# SCH_SDCARD-DOCK_2024-07-07.net
KiCad netlist of a schematic drawn in EasyEDA
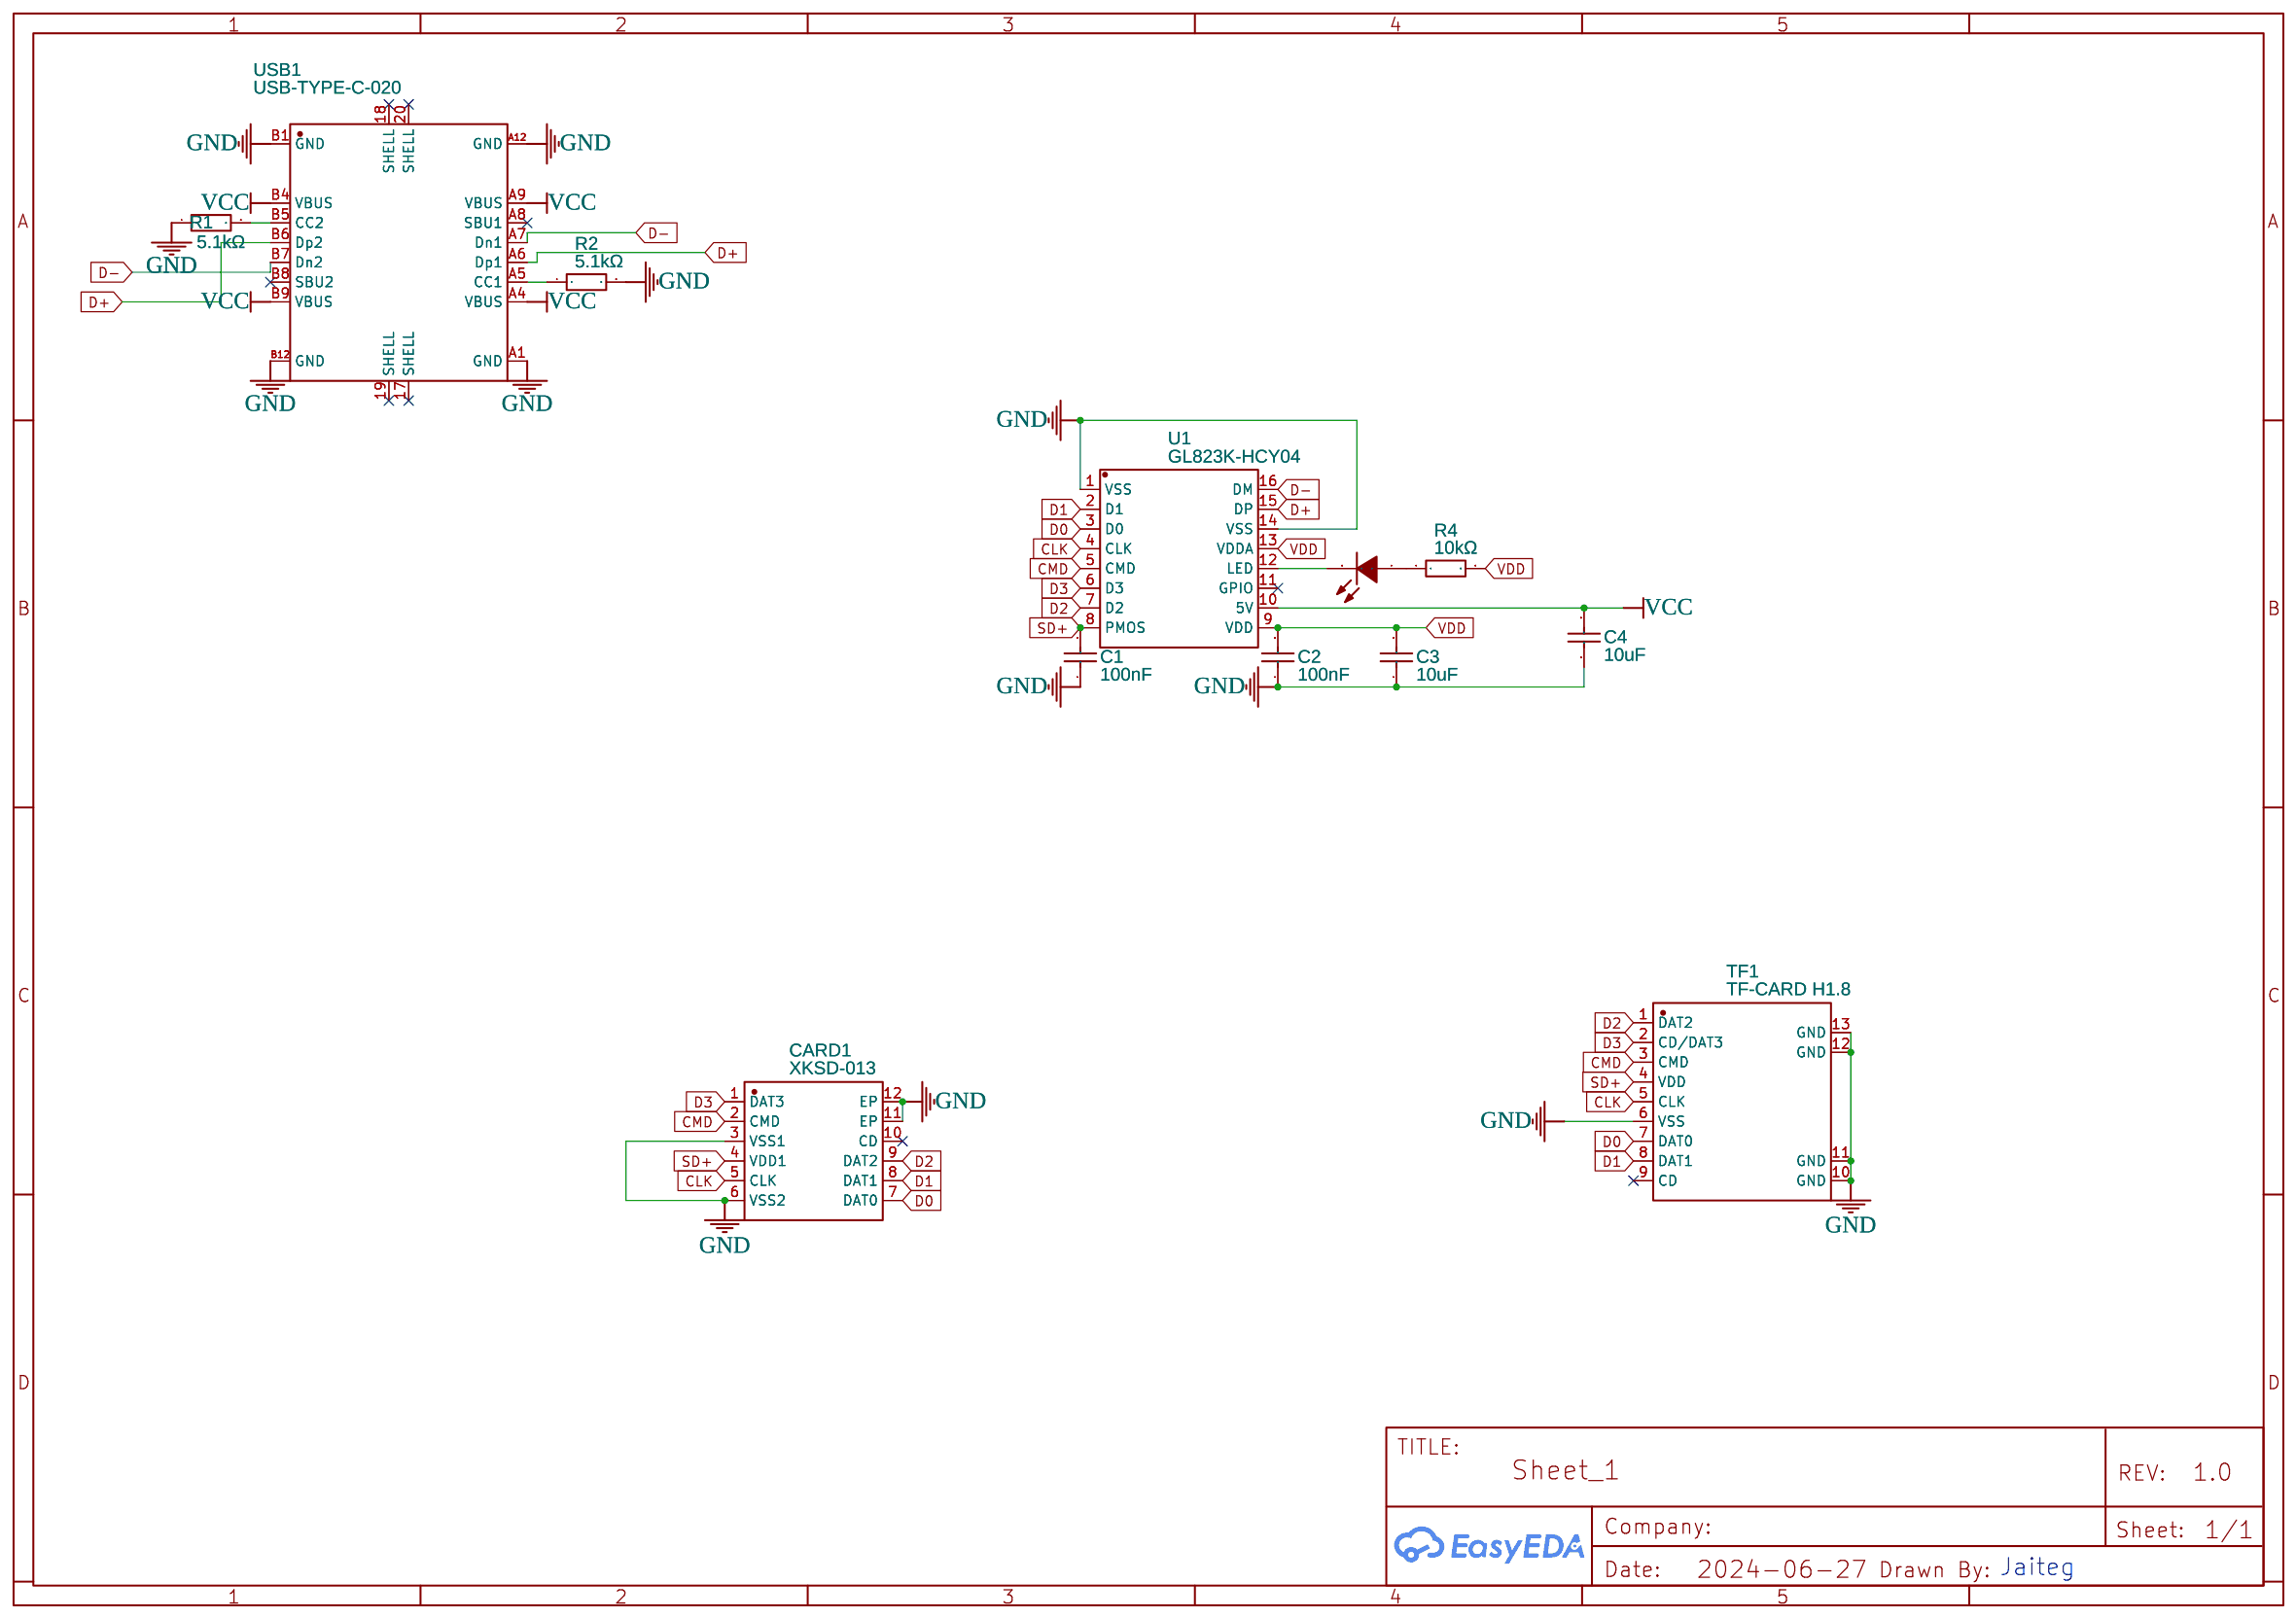
[diagram p0: schematic sheet]

(export (version "E")
  (design (tool "Eeschema 10.0.6"))
  (components
    (comp (ref "C1")
      (value "100nF")
      (fields
        (field (name "Manufacturer Part") "CL05B104KO5NNNC")
        (field (name "Manufacturer") "SAMSUNG(三星)")
      )
      (libsource (lib "") (part "CL05B104KO5NNNC"))
    )
    (comp (ref "C2")
      (value "100nF")
      (fields
        (field (name "Manufacturer Part") "CL05B104KO5NNNC")
        (field (name "Manufacturer") "SAMSUNG(三星)")
      )
      (libsource (lib "") (part "CL05B104KO5NNNC"))
    )
    (comp (ref "C3")
      (value "10uF")
      (fields
        (field (name "Manufacturer Part") "CL05A106MQ5NUNC")
        (field (name "Manufacturer") "SAMSUNG(三星)")
      )
      (libsource (lib "") (part "CL05A106MQ5NUNC"))
    )
    (comp (ref "C4")
      (value "10uF")
      (fields
        (field (name "Manufacturer Part") "CL05A106MQ5NUNC")
        (field (name "Manufacturer") "SAMSUNG(三星)")
      )
      (libsource (lib "") (part "CL05A106MQ5NUNC"))
    )
    (comp (ref "CARD1")
      (value "XKSD-013")
      (fields (field (name "Manufacturer") "XKB Connectivity(中国星坤)"))
      (libsource (lib "") (part "XKSD-013"))
    )
    (comp (ref "LED2")
      (value "0603White light_C2290")
      (fields (field (name "Manufacturer Part") "KT-0603白灯") (field (name "Manufacturer") "KENTO"))
      (libsource (lib "") (part "0603White light_C2290"))
    )
    (comp (ref "R1")
      (value "5.1kΩ")
      (fields
        (field (name "Manufacturer Part") "0402WGF5101TCE")
        (field (name "Manufacturer") "UNI-ROYAL(厚声)")
      )
      (libsource (lib "") (part "0402WGF5101TCE"))
    )
    (comp (ref "R2")
      (value "5.1kΩ")
      (fields
        (field (name "Manufacturer Part") "0402WGF5101TCE")
        (field (name "Manufacturer") "UNI-ROYAL(厚声)")
      )
      (libsource (lib "") (part "0402WGF5101TCE"))
    )
    (comp (ref "R4")
      (value "10kΩ")
      (fields
        (field (name "Manufacturer Part") "0805W8F1002T5E")
        (field (name "Manufacturer") "UNI-ROYAL(厚声)")
      )
      (libsource (lib "") (part "0805W8F1002T5E"))
    )
    (comp (ref "TF1")
      (value "TF-CARD H1.8")
      (fields (field (name "Manufacturer") "SHOU HAN(首韩)"))
      (libsource (lib "") (part "TF-CARD H1.8"))
    )
    (comp (ref "U1")
      (value "GL823K-HCY04")
      (fields (field (name "Manufacturer") "GENESYS(创惟)"))
      (libsource (lib "") (part "GL823K-HCY04"))
    )
    (comp (ref "USB1")
      (value "USB-TYPE-C-020")
      (fields (field (name "Manufacturer") "DEALON(德艺隆)"))
      (libsource (lib "") (part "USB-TYPE-C-020"))
    )
  )
  (nets
    (net (code "1") (name "CLK") (class "Default")
      (node (ref "CARD1") (pin "5") (pinfunction "CLK_5") (pintype "unspecified"))
      (node (ref "TF1") (pin "5") (pinfunction "CLK_5") (pintype "unspecified"))
      (node (ref "U1") (pin "4") (pinfunction "CLK_4") (pintype "unspecified"))
    )
    (net (code "2") (name "CMD") (class "Default")
      (node (ref "CARD1") (pin "2") (pinfunction "CMD_2") (pintype "unspecified"))
      (node (ref "TF1") (pin "3") (pinfunction "CMD_3") (pintype "unspecified"))
      (node (ref "U1") (pin "5") (pinfunction "CMD_5") (pintype "unspecified"))
    )
    (net (code "3") (name "D+") (class "Default")
      (node (ref "U1") (pin "15") (pinfunction "DP_15") (pintype "unspecified"))
      (node (ref "USB1") (pin "A6") (pinfunction "Dp1_A6") (pintype "unspecified"))
      (node (ref "USB1") (pin "B6") (pinfunction "Dp2_B6") (pintype "unspecified"))
    )
    (net (code "4") (name "D-") (class "Default")
      (node (ref "U1") (pin "16") (pinfunction "DM_16") (pintype "unspecified"))
      (node (ref "USB1") (pin "A7") (pinfunction "Dn1_A7") (pintype "unspecified"))
      (node (ref "USB1") (pin "B7") (pinfunction "Dn2_B7") (pintype "unspecified"))
    )
    (net (code "5") (name "D0") (class "Default")
      (node (ref "CARD1") (pin "7") (pinfunction "DAT0_7") (pintype "unspecified"))
      (node (ref "TF1") (pin "7") (pinfunction "DAT0_7") (pintype "unspecified"))
      (node (ref "U1") (pin "3") (pinfunction "D0_3") (pintype "unspecified"))
    )
    (net (code "6") (name "D1") (class "Default")
      (node (ref "CARD1") (pin "8") (pinfunction "DAT1_8") (pintype "unspecified"))
      (node (ref "TF1") (pin "8") (pinfunction "DAT1_8") (pintype "unspecified"))
      (node (ref "U1") (pin "2") (pinfunction "D1_2") (pintype "unspecified"))
    )
    (net (code "7") (name "D2") (class "Default")
      (node (ref "CARD1") (pin "9") (pinfunction "DAT2_9") (pintype "unspecified"))
      (node (ref "TF1") (pin "1") (pinfunction "DAT2_1") (pintype "unspecified"))
      (node (ref "U1") (pin "7") (pinfunction "D2_7") (pintype "unspecified"))
    )
    (net (code "8") (name "D3") (class "Default")
      (node (ref "CARD1") (pin "1") (pinfunction "DAT3_1") (pintype "unspecified"))
      (node (ref "TF1") (pin "2") (pinfunction "CD/DAT3_2") (pintype "unspecified"))
      (node (ref "U1") (pin "6") (pinfunction "D3_6") (pintype "unspecified"))
    )
    (net (code "9") (name "GND") (class "Default")
      (node (ref "C1") (pin "1") (pinfunction "1_1") (pintype "input"))
      (node (ref "C2") (pin "1") (pinfunction "1_1") (pintype "input"))
      (node (ref "C3") (pin "1") (pinfunction "1_1") (pintype "input"))
      (node (ref "C4") (pin "1") (pinfunction "1_1") (pintype "input"))
      (node (ref "CARD1") (pin "11") (pinfunction "EP_11") (pintype "unspecified"))
      (node (ref "CARD1") (pin "12") (pinfunction "EP_12") (pintype "unspecified"))
      (node (ref "CARD1") (pin "3") (pinfunction "VSS1_3") (pintype "unspecified"))
      (node (ref "CARD1") (pin "6") (pinfunction "VSS2_6") (pintype "unspecified"))
      (node (ref "R1") (pin "1") (pinfunction "1_1") (pintype "input"))
      (node (ref "R2") (pin "2") (pinfunction "2_2") (pintype "input"))
      (node (ref "TF1") (pin "10") (pinfunction "GND_10") (pintype "unspecified"))
      (node (ref "TF1") (pin "11") (pinfunction "GND_11") (pintype "unspecified"))
      (node (ref "TF1") (pin "12") (pinfunction "GND_12") (pintype "unspecified"))
      (node (ref "TF1") (pin "13") (pinfunction "GND_13") (pintype "unspecified"))
      (node (ref "TF1") (pin "6") (pinfunction "VSS_6") (pintype "unspecified"))
      (node (ref "U1") (pin "1") (pinfunction "VSS_1") (pintype "unspecified"))
      (node (ref "U1") (pin "14") (pinfunction "VSS_14") (pintype "unspecified"))
      (node (ref "USB1") (pin "A1") (pinfunction "GND_A1") (pintype "unspecified"))
      (node (ref "USB1") (pin "A12") (pinfunction "GND_A12") (pintype "unspecified"))
      (node (ref "USB1") (pin "B1") (pinfunction "GND_B1") (pintype "unspecified"))
      (node (ref "USB1") (pin "B12") (pinfunction "GND_B12") (pintype "unspecified"))
    )
    (net (code "10") (name "Net-(LED2-A)") (class "Default")
      (node (ref "LED2") (pin "1") (pinfunction "A_1") (pintype "unspecified"))
      (node (ref "R4") (pin "1") (pinfunction "1_1") (pintype "input"))
    )
    (net (code "11") (name "Net-(LED2-K)") (class "Default")
      (node (ref "LED2") (pin "2") (pinfunction "K_2") (pintype "unspecified"))
      (node (ref "U1") (pin "12") (pinfunction "LED_12") (pintype "unspecified"))
    )
    (net (code "12") (name "Net-(USB1-CC1)") (class "Default")
      (node (ref "R2") (pin "1") (pinfunction "1_1") (pintype "input"))
      (node (ref "USB1") (pin "A5") (pinfunction "CC1_A5") (pintype "unspecified"))
    )
    (net (code "13") (name "Net-(USB1-CC2)") (class "Default")
      (node (ref "R1") (pin "2") (pinfunction "2_2") (pintype "input"))
      (node (ref "USB1") (pin "B5") (pinfunction "CC2_B5") (pintype "unspecified"))
    )
    (net (code "14") (name "SD+") (class "Default")
      (node (ref "C1") (pin "2") (pinfunction "2_2") (pintype "input"))
      (node (ref "CARD1") (pin "4") (pinfunction "VDD1_4") (pintype "unspecified"))
      (node (ref "TF1") (pin "4") (pinfunction "VDD_4") (pintype "unspecified"))
      (node (ref "U1") (pin "8") (pinfunction "PMOS_8") (pintype "unspecified"))
    )
    (net (code "15") (name "VCC") (class "Default")
      (node (ref "C4") (pin "2") (pinfunction "2_2") (pintype "input"))
      (node (ref "U1") (pin "10") (pinfunction "5V_10") (pintype "unspecified"))
      (node (ref "USB1") (pin "A4") (pinfunction "VBUS_A4") (pintype "unspecified"))
      (node (ref "USB1") (pin "A9") (pinfunction "VBUS_A9") (pintype "unspecified"))
      (node (ref "USB1") (pin "B4") (pinfunction "VBUS_B4") (pintype "unspecified"))
      (node (ref "USB1") (pin "B9") (pinfunction "VBUS_B9") (pintype "unspecified"))
    )
    (net (code "16") (name "VDD") (class "Default")
      (node (ref "C2") (pin "2") (pinfunction "2_2") (pintype "input"))
      (node (ref "C3") (pin "2") (pinfunction "2_2") (pintype "input"))
      (node (ref "R4") (pin "2") (pinfunction "2_2") (pintype "input"))
      (node (ref "U1") (pin "13") (pinfunction "VDDA_13") (pintype "unspecified"))
      (node (ref "U1") (pin "9") (pinfunction "VDD_9") (pintype "unspecified"))
    )
    (net (code "17") (name "unconnected-(CARD1-CD-Pad10)") (class "Default")
      (node (ref "CARD1") (pin "10") (pinfunction "CD_10") (pintype "unspecified+no_connect"))
    )
    (net (code "18") (name "unconnected-(TF1-CD-Pad9)") (class "Default")
      (node (ref "TF1") (pin "9") (pinfunction "CD_9") (pintype "unspecified+no_connect"))
    )
    (net (code "19") (name "unconnected-(U1-GPIO-Pad11)") (class "Default")
      (node (ref "U1") (pin "11") (pinfunction "GPIO_11") (pintype "unspecified+no_connect"))
    )
    (net (code "20") (name "unconnected-(USB1-SBU1-PadA8)") (class "Default")
      (node (ref "USB1") (pin "A8") (pinfunction "SBU1_A8") (pintype "unspecified+no_connect"))
    )
    (net (code "21") (name "unconnected-(USB1-SBU2-PadB8)") (class "Default")
      (node (ref "USB1") (pin "B8") (pinfunction "SBU2_B8") (pintype "unspecified+no_connect"))
    )
    (net (code "22") (name "unconnected-(USB1-SHELL-Pad17)") (class "Default")
      (node (ref "USB1") (pin "17") (pinfunction "SHELL_17") (pintype "unspecified+no_connect"))
    )
    (net (code "23") (name "unconnected-(USB1-SHELL-Pad18)") (class "Default")
      (node (ref "USB1") (pin "18") (pinfunction "SHELL_18") (pintype "unspecified+no_connect"))
    )
    (net (code "24") (name "unconnected-(USB1-SHELL-Pad19)") (class "Default")
      (node (ref "USB1") (pin "19") (pinfunction "SHELL_19") (pintype "unspecified+no_connect"))
    )
    (net (code "25") (name "unconnected-(USB1-SHELL-Pad20)") (class "Default")
      (node (ref "USB1") (pin "20") (pinfunction "SHELL_20") (pintype "unspecified+no_connect"))
    )
  )
)
